# mpu6050.net
KiCad netlist of a schematic drawn in Altium Designer
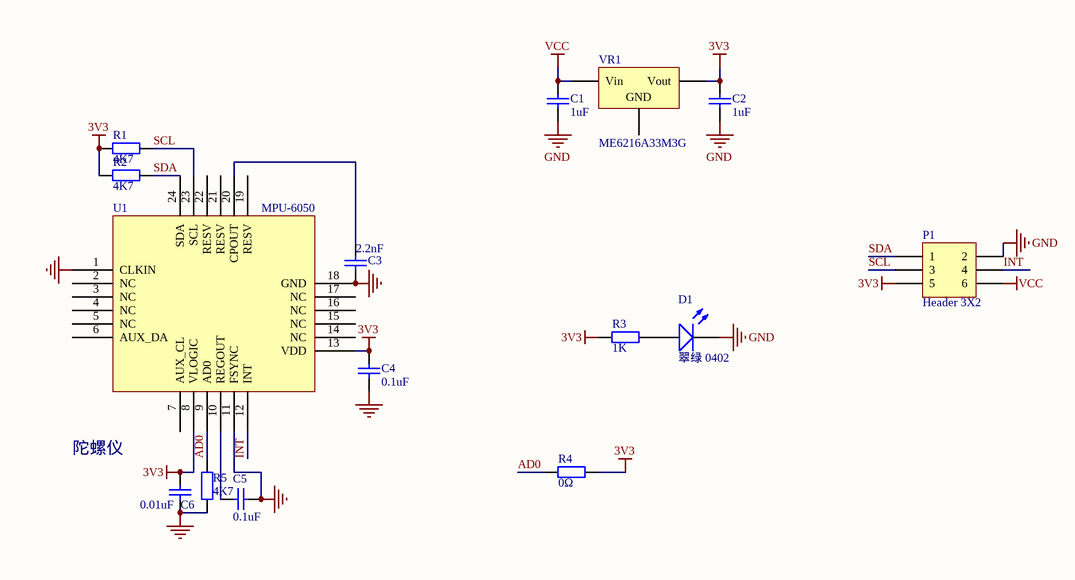
[diagram p0: mpu6050单模块.SchDoc]

(export (version "E")
  (design (tool "Eeschema 10.0.6"))
  (components
    (comp (ref "C1")
      (value "1uF")
      (footprint "0402_C")
      (description "0402贴片电容")
      (libsource (lib "02-Miscellaneous_Devices_ZSF_Library") (part "Cap_0402"))
    )
    (comp (ref "C2")
      (value "1uF")
      (footprint "0402_C")
      (description "0402贴片电容")
      (libsource (lib "02-Miscellaneous_Devices_ZSF_Library") (part "Cap_0402"))
    )
    (comp (ref "C3")
      (value "2.2nF")
      (footprint "0402_C")
      (description "0402贴片电容")
      (libsource (lib "02-Miscellaneous_Devices_ZSF_Library") (part "Cap_0402"))
    )
    (comp (ref "C4")
      (value "0.1uF")
      (footprint "0402_C")
      (description "0402贴片电容")
      (libsource (lib "02-Miscellaneous_Devices_ZSF_Library") (part "Cap_0402"))
    )
    (comp (ref "C5")
      (value "0.1uF")
      (footprint "0402_C")
      (description "0402贴片电容")
      (libsource (lib "02-Miscellaneous_Devices_ZSF_Library") (part "Cap_0402"))
    )
    (comp (ref "C6")
      (value "0.01uF")
      (footprint "0402_C")
      (description "0402贴片电容")
      (libsource (lib "02-Miscellaneous_Devices_ZSF_Library") (part "Cap_0402"))
    )
    (comp (ref "D1")
      (value "翠绿 0402")
      (footprint "0402 LED")
      (description "发光二极管")
      (libsource (lib "02-Miscellaneous_Devices_ZSF_Library") (part "0603 白灯"))
    )
    (comp (ref "P1")
      (value "Header 3X2")
      (footprint "贴片排针2X3P")
      (description "Header, 3-Pin, Dual row")
      (fields (field (name "PUBLISHER") "Altium Limited"))
      (libsource (lib "常用元件集成库") (part "Header 3X2"))
    )
    (comp (ref "R1")
      (value "4K7")
      (footprint "0402_R")
      (description "贴片电阻")
      (libsource (lib "") (part "Res_0402_1"))
    )
    (comp (ref "R2")
      (value "4K7")
      (footprint "0402_R")
      (description "贴片电阻")
      (libsource (lib "") (part "Res_0402_1"))
    )
    (comp (ref "R3")
      (value "1K")
      (footprint "0402_R")
      (description "贴片电阻")
      (libsource (lib "") (part "Res_0402_2"))
    )
    (comp (ref "R4")
      (value "0Ω")
      (footprint "0402_R")
      (description "贴片电阻")
      (libsource (lib "") (part "Res_0402_2"))
    )
    (comp (ref "R5")
      (value "4K7")
      (footprint "0402_R")
      (description "贴片电阻")
      (libsource (lib "02-Miscellaneous_Devices_ZSF_Library") (part "Res_0402"))
    )
    (comp (ref "U1")
      (value "MPU-6050")
      (footprint "QFN-24_4x4x05P")
      (description "传感器")
      (libsource (lib "02-Miscellaneous_Devices_ZSF_Library") (part "MPU-6050"))
    )
    (comp (ref "VR1")
      (value "ME6216A33M3G")
      (footprint "ME6216A33M3G")
      (description "低压差线性稳压(LDO)")
      (libsource (lib "02-Miscellaneous_Devices_ZSF_Library") (part "XC6206P332MR  SOT-23"))
    )
  )
  (nets
    (net (code "1") (name "/AD0") (class "Default")
      (node (ref "R4") (pin "1") (pinfunction "1_1") (pintype "passive"))
      (node (ref "R5") (pin "2") (pinfunction "2_2") (pintype "passive"))
      (node (ref "U1") (pin "9") (pinfunction "AD0_9") (pintype "passive"))
    )
    (net (code "2") (name "/INT") (class "Default")
      (node (ref "P1") (pin "4") (pinfunction "4_4") (pintype "passive"))
      (node (ref "U1") (pin "12") (pinfunction "INT_12") (pintype "passive"))
    )
    (net (code "3") (name "/SCL") (class "Default")
      (node (ref "P1") (pin "3") (pinfunction "3_3") (pintype "passive"))
      (node (ref "R1") (pin "1") (pinfunction "1_1") (pintype "passive"))
      (node (ref "U1") (pin "23") (pinfunction "SCL_23") (pintype "passive"))
    )
    (net (code "4") (name "/SDA") (class "Default")
      (node (ref "P1") (pin "1") (pinfunction "1_1") (pintype "passive"))
      (node (ref "R2") (pin "1") (pinfunction "1_1") (pintype "passive"))
      (node (ref "U1") (pin "24") (pinfunction "SDA_24") (pintype "passive"))
    )
    (net (code "5") (name "3V3") (class "Default")
      (node (ref "C2") (pin "2") (pinfunction "2_2") (pintype "passive"))
      (node (ref "C4") (pin "2") (pinfunction "2_2") (pintype "passive"))
      (node (ref "C6") (pin "1") (pinfunction "1_1") (pintype "passive"))
      (node (ref "P1") (pin "5") (pinfunction "5_5") (pintype "passive"))
      (node (ref "R1") (pin "2") (pinfunction "2_2") (pintype "passive"))
      (node (ref "R2") (pin "2") (pinfunction "2_2") (pintype "passive"))
      (node (ref "R3") (pin "1") (pinfunction "1_1") (pintype "passive"))
      (node (ref "R4") (pin "2") (pinfunction "2_2") (pintype "passive"))
      (node (ref "U1") (pin "13") (pinfunction "VDD_13") (pintype "passive"))
      (node (ref "U1") (pin "8") (pinfunction "VLOGIC_8") (pintype "passive"))
      (node (ref "VR1") (pin "2") (pinfunction "Vout_2") (pintype "passive"))
    )
    (net (code "6") (name "GND") (class "Default")
      (node (ref "C1") (pin "1") (pinfunction "1_1") (pintype "passive"))
      (node (ref "C2") (pin "1") (pinfunction "1_1") (pintype "passive"))
      (node (ref "C3") (pin "1") (pinfunction "1_1") (pintype "passive"))
      (node (ref "C4") (pin "1") (pinfunction "1_1") (pintype "passive"))
      (node (ref "C5") (pin "1") (pinfunction "1_1") (pintype "passive"))
      (node (ref "C6") (pin "2") (pinfunction "2_2") (pintype "passive"))
      (node (ref "D1") (pin "K") (pinfunction "K_K") (pintype "passive"))
      (node (ref "P1") (pin "2") (pinfunction "2_2") (pintype "passive"))
      (node (ref "R5") (pin "1") (pinfunction "1_1") (pintype "passive"))
      (node (ref "U1") (pin "1") (pinfunction "CLKIN_1") (pintype "passive"))
      (node (ref "U1") (pin "11") (pinfunction "FSYNC_11") (pintype "passive"))
      (node (ref "U1") (pin "18") (pinfunction "GND_18") (pintype "passive"))
    )
    (net (code "7") (name "Net-(D1-PadA)") (class "Default")
      (node (ref "D1") (pin "A") (pinfunction "A_A") (pintype "passive"))
      (node (ref "R3") (pin "2") (pinfunction "2_2") (pintype "passive"))
    )
    (net (code "8") (name "Net-(U1-CPOUT)") (class "Default")
      (node (ref "C3") (pin "2") (pinfunction "2_2") (pintype "passive"))
      (node (ref "U1") (pin "20") (pinfunction "CPOUT_20") (pintype "passive"))
    )
    (net (code "9") (name "Net-(U1-REGOUT)") (class "Default")
      (node (ref "C5") (pin "2") (pinfunction "2_2") (pintype "passive"))
      (node (ref "U1") (pin "10") (pinfunction "REGOUT_10") (pintype "passive"))
    )
    (net (code "10") (name "VCC") (class "Default")
      (node (ref "C1") (pin "2") (pinfunction "2_2") (pintype "passive"))
      (node (ref "P1") (pin "6") (pinfunction "6_6") (pintype "passive"))
      (node (ref "VR1") (pin "3") (pinfunction "Vin_3") (pintype "passive"))
    )
    (net (code "11") (name "unconnected-(U1-AUX_CL-Pad7)") (class "Default")
      (node (ref "U1") (pin "7") (pinfunction "AUX_CL_7") (pintype "passive"))
    )
    (net (code "12") (name "unconnected-(U1-AUX_DA-Pad6)") (class "Default")
      (node (ref "U1") (pin "6") (pinfunction "AUX_DA_6") (pintype "passive"))
    )
    (net (code "13") (name "unconnected-(U1-NC-Pad2)") (class "Default")
      (node (ref "U1") (pin "2") (pinfunction "NC_2") (pintype "passive"))
    )
    (net (code "14") (name "unconnected-(U1-NC-Pad3)") (class "Default")
      (node (ref "U1") (pin "3") (pinfunction "NC_3") (pintype "passive"))
    )
    (net (code "15") (name "unconnected-(U1-NC-Pad4)") (class "Default")
      (node (ref "U1") (pin "4") (pinfunction "NC_4") (pintype "passive"))
    )
    (net (code "16") (name "unconnected-(U1-NC-Pad5)") (class "Default")
      (node (ref "U1") (pin "5") (pinfunction "NC_5") (pintype "passive"))
    )
    (net (code "17") (name "unconnected-(U1-NC-Pad14)") (class "Default")
      (node (ref "U1") (pin "14") (pinfunction "NC_14") (pintype "passive"))
    )
    (net (code "18") (name "unconnected-(U1-NC-Pad15)") (class "Default")
      (node (ref "U1") (pin "15") (pinfunction "NC_15") (pintype "passive"))
    )
    (net (code "19") (name "unconnected-(U1-NC-Pad16)") (class "Default")
      (node (ref "U1") (pin "16") (pinfunction "NC_16") (pintype "passive"))
    )
    (net (code "20") (name "unconnected-(U1-NC-Pad17)") (class "Default")
      (node (ref "U1") (pin "17") (pinfunction "NC_17") (pintype "passive"))
    )
    (net (code "21") (name "unconnected-(U1-RESV-Pad19)") (class "Default")
      (node (ref "U1") (pin "19") (pinfunction "RESV_19") (pintype "passive"))
    )
    (net (code "22") (name "unconnected-(U1-RESV-Pad21)") (class "Default")
      (node (ref "U1") (pin "21") (pinfunction "RESV_21") (pintype "passive"))
    )
    (net (code "23") (name "unconnected-(U1-RESV-Pad22)") (class "Default")
      (node (ref "U1") (pin "22") (pinfunction "RESV_22") (pintype "passive"))
    )
    (net (code "24") (name "unconnected-(VR1-GND-Pad1)") (class "Default")
      (node (ref "VR1") (pin "1") (pinfunction "GND_1") (pintype "passive"))
    )
  )
)
